# USB_Input.net
KiCad netlist of a schematic drawn in Altium Designer
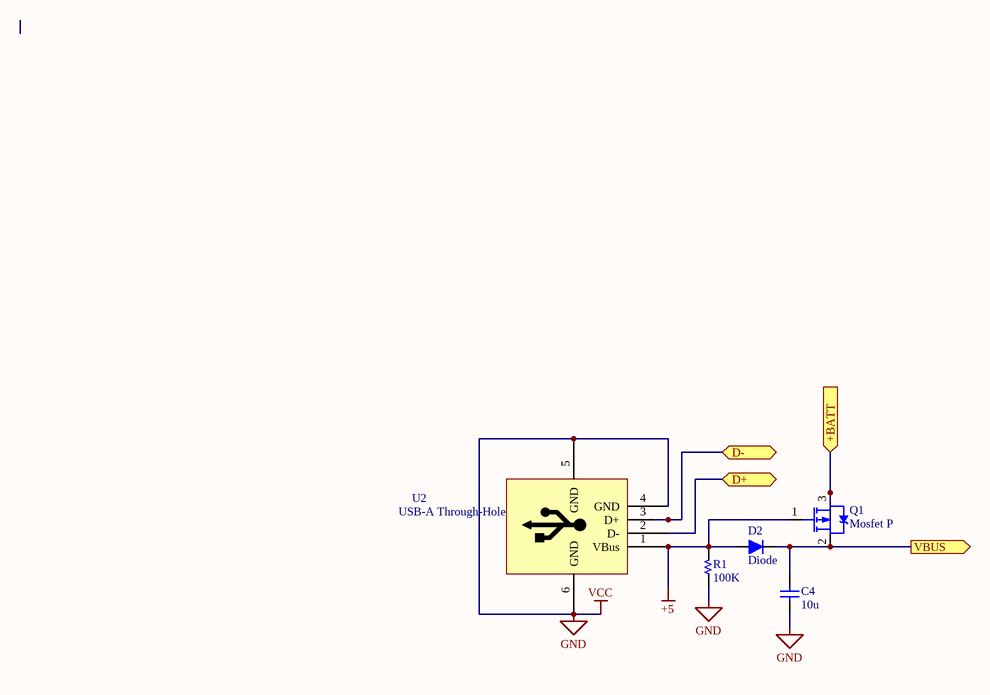
[diagram p0: USB Input.SchDoc]

(export (version "E")
  (design (tool "Eeschema 10.0.6"))
  (components
    (comp (ref "C4")
      (value "10u")
      (footprint "C 0805")
      (description "Capacitor non-pol")
      (libsource (lib "chipfc_libs") (part "Capacitor NP"))
    )
    (comp (ref "D2")
      (value "Diode")
      (footprint "DO-35 (SOD27 )")
      (description "Default Diode")
      (libsource (lib "chipfc_libs") (part "Diode"))
    )
    (comp (ref "Q1")
      (value "Mosfet P")
      (footprint "SOT-23")
      (libsource (lib "chipfc_libs") (part "Mosfet P"))
    )
    (comp (ref "R1")
      (value "100K")
      (footprint "R 0805")
      (description "Resistor")
      (libsource (lib "chipfc_libs") (part "Resistor"))
    )
    (comp (ref "U2")
      (value "USB-A Through-Hole")
      (footprint "USB-A")
      (libsource (lib "Devzone_SCHLib") (part "USB-A TH"))
    )
  )
  (nets
    (net (code "1") (name "+5") (class "Default")
      (node (ref "D2") (pin "1") (pinfunction "A_1") (pintype "passive"))
      (node (ref "Q1") (pin "1") (pinfunction "G_1") (pintype "passive"))
      (node (ref "R1") (pin "2") (pinfunction "2_2") (pintype "passive"))
      (node (ref "U2") (pin "1") (pinfunction "VBus_1") (pintype "passive"))
    )
    (net (code "2") (name "/+BATT") (class "Default")
      (node (ref "Q1") (pin "3") (pinfunction "D_3") (pintype "passive"))
    )
    (net (code "3") (name "/D+") (class "Default")
      (node (ref "U2") (pin "2") (pinfunction "D-_2") (pintype "passive"))
    )
    (net (code "4") (name "/D-") (class "Default")
      (node (ref "U2") (pin "3") (pinfunction "D+_3") (pintype "passive"))
    )
    (net (code "5") (name "/VBUS") (class "Default")
      (node (ref "C4") (pin "1") (pinfunction "1_1") (pintype "passive"))
      (node (ref "D2") (pin "2") (pinfunction "K_2") (pintype "passive"))
      (node (ref "Q1") (pin "2") (pinfunction "S_2") (pintype "passive"))
    )
    (net (code "6") (name "GND") (class "Default")
      (node (ref "C4") (pin "2") (pinfunction "2_2") (pintype "passive"))
      (node (ref "R1") (pin "1") (pinfunction "1_1") (pintype "passive"))
      (node (ref "U2") (pin "4") (pinfunction "GND_4") (pintype "passive"))
      (node (ref "U2") (pin "5") (pinfunction "GND_5") (pintype "passive"))
      (node (ref "U2") (pin "6") (pinfunction "GND_6") (pintype "passive"))
    )
  )
)
